# CenteredLighthouseCircuit.net
KiCad netlist of a schematic drawn in EAGLE
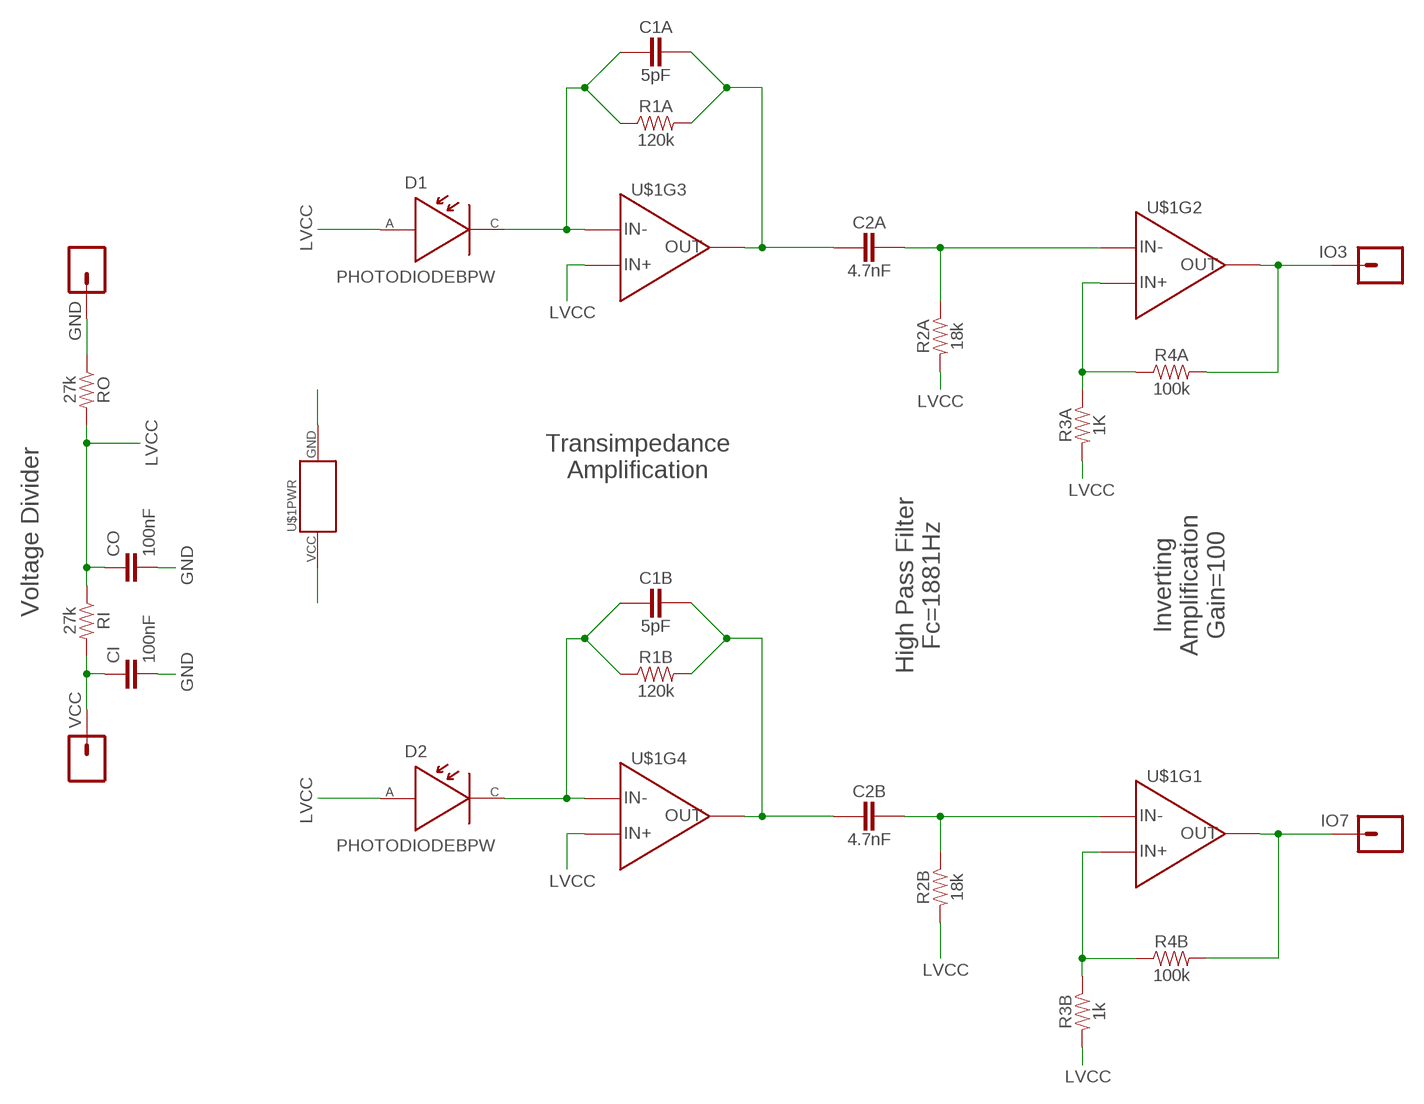
[diagram p0: schematic, sheet 1]

(export (version "E")
  (design (tool "Eeschema 10.0.6"))
  (components
    (comp (ref "C1A")
      (value "5pF")
      (footprint "eagle-import:PASSIVE-0603")
      (libsource (lib "eagle-import") (part "CAPACITOR"))
    )
    (comp (ref "C1B")
      (value "5pF")
      (footprint "eagle-import:PASSIVE-0603")
      (libsource (lib "eagle-import") (part "CAPACITOR"))
    )
    (comp (ref "C2A")
      (value "4.7nF")
      (footprint "eagle-import:PASSIVE-0603")
      (libsource (lib "eagle-import") (part "CAPACITOR"))
    )
    (comp (ref "C2B")
      (value "4.7nF")
      (footprint "eagle-import:PASSIVE-0603")
      (libsource (lib "eagle-import") (part "CAPACITOR"))
    )
    (comp (ref "CI")
      (value "100nF")
      (footprint "eagle-import:0603")
      (libsource (lib "eagle-import") (part "4.7PF-0603-50V-5%"))
    )
    (comp (ref "CO")
      (value "100nF")
      (footprint "eagle-import:0603")
      (libsource (lib "eagle-import") (part "4.7PF-0603-50V-5%"))
    )
    (comp (ref "D1")
      (value "PHOTODIODEBPW")
      (footprint "eagle-import:BPW34_BP104_SMD")
      (libsource (lib "eagle-import") (part "PHOTODIODEBPW"))
    )
    (comp (ref "D2")
      (value "PHOTODIODEBPW")
      (footprint "eagle-import:BPW34_BP104_SMD")
      (libsource (lib "eagle-import") (part "PHOTODIODEBPW"))
    )
    (comp (ref "GND")
      (value "CONN_01PTH_NO_SILK_YES_STOP")
      (footprint "eagle-import:1X01_NO_SILK")
      (libsource (lib "eagle-import") (part "CONN_01PTH_NO_SILK_YES_STOP"))
    )
    (comp (ref "IO3")
      (value "CONN_01PTH_NO_SILK_YES_STOP")
      (footprint "eagle-import:1X01_NO_SILK")
      (libsource (lib "eagle-import") (part "CONN_01PTH_NO_SILK_YES_STOP"))
    )
    (comp (ref "IO7")
      (value "CONN_01PTH_NO_SILK_YES_STOP")
      (footprint "eagle-import:1X01_NO_SILK")
      (libsource (lib "eagle-import") (part "CONN_01PTH_NO_SILK_YES_STOP"))
    )
    (comp (ref "R1A")
      (value "120k")
      (footprint "eagle-import:PASSIVE-0603")
      (libsource (lib "eagle-import") (part "RESISTOR"))
    )
    (comp (ref "R1B")
      (value "120k")
      (footprint "eagle-import:PASSIVE-0603")
      (libsource (lib "eagle-import") (part "RESISTOR"))
    )
    (comp (ref "R2A")
      (value "18k")
      (footprint "eagle-import:PASSIVE-0603")
      (libsource (lib "eagle-import") (part "RESISTOR"))
    )
    (comp (ref "R2B")
      (value "18k")
      (footprint "eagle-import:PASSIVE-0603")
      (libsource (lib "eagle-import") (part "RESISTOR"))
    )
    (comp (ref "R3A")
      (value "1K")
      (footprint "eagle-import:PASSIVE-0603")
      (libsource (lib "eagle-import") (part "RESISTOR"))
    )
    (comp (ref "R3B")
      (value "1k")
      (footprint "eagle-import:PASSIVE-0603")
      (libsource (lib "eagle-import") (part "RESISTOR"))
    )
    (comp (ref "R4A")
      (value "100k")
      (footprint "eagle-import:PASSIVE-0603")
      (libsource (lib "eagle-import") (part "RESISTOR"))
    )
    (comp (ref "R4B")
      (value "100k")
      (footprint "eagle-import:PASSIVE-0603")
      (libsource (lib "eagle-import") (part "RESISTOR"))
    )
    (comp (ref "RI")
      (value "27k")
      (footprint "eagle-import:0603")
      (libsource (lib "eagle-import") (part "100KOHM-0603-1/10W-1%"))
    )
    (comp (ref "RO")
      (value "27k")
      (footprint "eagle-import:0603")
      (libsource (lib "eagle-import") (part "100KOHM-0603-1/10W-1%"))
    )
    (comp (ref "U$1")
      (value "TLV2464IPW")
      (footprint "eagle-import:PW14")
      (libsource (lib "eagle-import") (part "TLV2464IPW"))
    )
    (comp (ref "VCC")
      (value "CONN_01PTH_NO_SILK_YES_STOP")
      (footprint "eagle-import:1X01_NO_SILK")
      (libsource (lib "eagle-import") (part "CONN_01PTH_NO_SILK_YES_STOP"))
    )
  )
  (nets
    (net (code "1") (name "/GND") (class "Default")
      (node (ref "CI") (pin "2") (pinfunction "2_2") (pintype "passive"))
      (node (ref "CO") (pin "2") (pinfunction "2_2") (pintype "passive"))
      (node (ref "GND") (pin "1") (pinfunction "1_1") (pintype "passive"))
      (node (ref "RO") (pin "1") (pinfunction "1_1") (pintype "passive"))
      (node (ref "U$1") (pin "11") (pinfunction "GND_11") (pintype "bidirectional"))
    )
    (net (code "2") (name "/IO3") (class "Default")
      (node (ref "IO3") (pin "1") (pinfunction "1_1") (pintype "passive"))
      (node (ref "R4A") (pin "2") (pinfunction "2_2") (pintype "passive"))
      (node (ref "U$1") (pin "7") (pinfunction "OUT_7") (pintype "bidirectional"))
    )
    (net (code "3") (name "/IO7") (class "Default")
      (node (ref "IO7") (pin "1") (pinfunction "1_1") (pintype "passive"))
      (node (ref "R4B") (pin "2") (pinfunction "2_2") (pintype "passive"))
      (node (ref "U$1") (pin "1") (pinfunction "OUT_1") (pintype "bidirectional"))
    )
    (net (code "4") (name "/LVCC") (class "Default")
      (node (ref "CO") (pin "1") (pinfunction "1_1") (pintype "passive"))
      (node (ref "D1") (pin "ANODE") (pinfunction "ANODE_ANODE") (pintype "bidirectional"))
      (node (ref "D2") (pin "ANODE") (pinfunction "ANODE_ANODE") (pintype "bidirectional"))
      (node (ref "R2A") (pin "2") (pinfunction "2_2") (pintype "passive"))
      (node (ref "R2B") (pin "2") (pinfunction "2_2") (pintype "passive"))
      (node (ref "R3A") (pin "2") (pinfunction "2_2") (pintype "passive"))
      (node (ref "R3B") (pin "2") (pinfunction "2_2") (pintype "passive"))
      (node (ref "RI") (pin "1") (pinfunction "1_1") (pintype "passive"))
      (node (ref "RO") (pin "2") (pinfunction "2_2") (pintype "passive"))
      (node (ref "U$1") (pin "10") (pinfunction "IN+_10") (pintype "bidirectional"))
      (node (ref "U$1") (pin "12") (pinfunction "IN+_12") (pintype "bidirectional"))
    )
    (net (code "5") (name "/VCC") (class "Default")
      (node (ref "CI") (pin "1") (pinfunction "1_1") (pintype "passive"))
      (node (ref "RI") (pin "2") (pinfunction "2_2") (pintype "passive"))
      (node (ref "U$1") (pin "4") (pinfunction "VCC_4") (pintype "bidirectional"))
      (node (ref "VCC") (pin "1") (pinfunction "1_1") (pintype "passive"))
    )
    (net (code "6") (name "Net-(U$1A-IN+)") (class "Default")
      (node (ref "R3B") (pin "1") (pinfunction "1_1") (pintype "passive"))
      (node (ref "R4B") (pin "1") (pinfunction "1_1") (pintype "passive"))
      (node (ref "U$1") (pin "3") (pinfunction "IN+_3") (pintype "bidirectional"))
    )
    (net (code "7") (name "Net-(U$1A-IN-)") (class "Default")
      (node (ref "C2B") (pin "2") (pinfunction "2_2") (pintype "passive"))
      (node (ref "R2B") (pin "1") (pinfunction "1_1") (pintype "passive"))
      (node (ref "U$1") (pin "2") (pinfunction "IN-_2") (pintype "bidirectional"))
    )
    (net (code "8") (name "Net-(U$1B-IN+)") (class "Default")
      (node (ref "R3A") (pin "1") (pinfunction "1_1") (pintype "passive"))
      (node (ref "R4A") (pin "1") (pinfunction "1_1") (pintype "passive"))
      (node (ref "U$1") (pin "5") (pinfunction "IN+_5") (pintype "bidirectional"))
    )
    (net (code "9") (name "Net-(U$1B-IN-)") (class "Default")
      (node (ref "C2A") (pin "2") (pinfunction "2_2") (pintype "passive"))
      (node (ref "R2A") (pin "1") (pinfunction "1_1") (pintype "passive"))
      (node (ref "U$1") (pin "6") (pinfunction "IN-_6") (pintype "bidirectional"))
    )
    (net (code "10") (name "Net-(U$1C-IN-)") (class "Default")
      (node (ref "C1A") (pin "1") (pinfunction "1_1") (pintype "passive"))
      (node (ref "D1") (pin "CATHODE") (pinfunction "CATHODE_CATHODE") (pintype "bidirectional"))
      (node (ref "R1A") (pin "1") (pinfunction "1_1") (pintype "passive"))
      (node (ref "U$1") (pin "9") (pinfunction "IN-_9") (pintype "bidirectional"))
    )
    (net (code "11") (name "Net-(U$1C-OUT)") (class "Default")
      (node (ref "C1A") (pin "2") (pinfunction "2_2") (pintype "passive"))
      (node (ref "C2A") (pin "1") (pinfunction "1_1") (pintype "passive"))
      (node (ref "R1A") (pin "2") (pinfunction "2_2") (pintype "passive"))
      (node (ref "U$1") (pin "8") (pinfunction "OUT_8") (pintype "bidirectional"))
    )
    (net (code "12") (name "Net-(U$1D-IN-)") (class "Default")
      (node (ref "C1B") (pin "1") (pinfunction "1_1") (pintype "passive"))
      (node (ref "D2") (pin "CATHODE") (pinfunction "CATHODE_CATHODE") (pintype "bidirectional"))
      (node (ref "R1B") (pin "1") (pinfunction "1_1") (pintype "passive"))
      (node (ref "U$1") (pin "13") (pinfunction "IN-_13") (pintype "bidirectional"))
    )
    (net (code "13") (name "Net-(U$1D-OUT)") (class "Default")
      (node (ref "C1B") (pin "2") (pinfunction "2_2") (pintype "passive"))
      (node (ref "C2B") (pin "1") (pinfunction "1_1") (pintype "passive"))
      (node (ref "R1B") (pin "2") (pinfunction "2_2") (pintype "passive"))
      (node (ref "U$1") (pin "14") (pinfunction "OUT_14") (pintype "bidirectional"))
    )
  )
)
